# tag.net
KiCad netlist of a schematic drawn in EAGLE
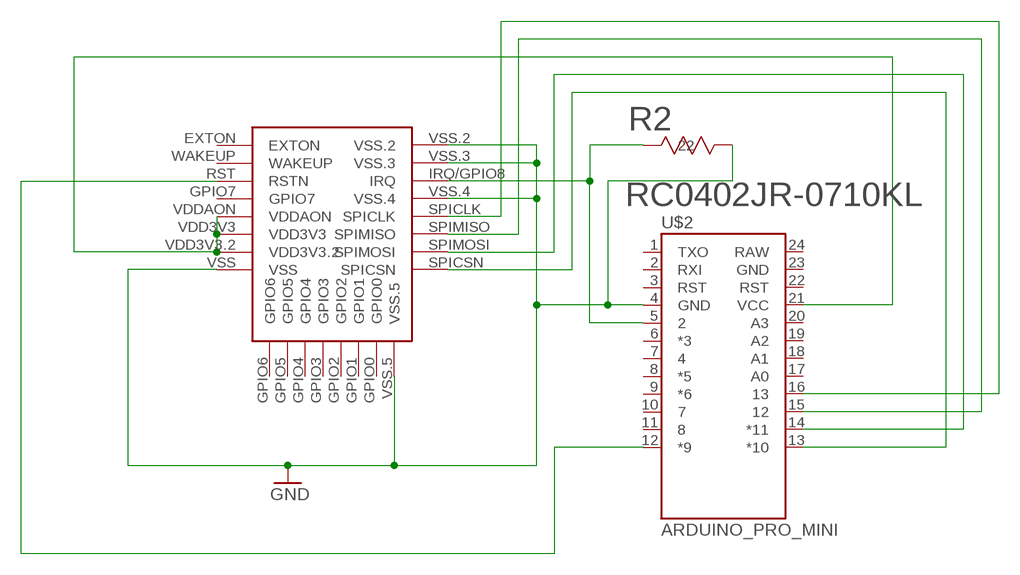
[diagram p0: schematic, sheet 1]

(export (version "E")
  (design (tool "Eeschema 10.0.6"))
  (components
    (comp (ref "R2")
      (value "RC0402JR-0710KL")
      (footprint "eagle-import:RC0402N")
      (fields
        (field (name "DIGIKEYPARTNUMBER") "31110KJRTRND")
        (field (name "MANUFACTURER_PART_NUMBER") "RC0402JR0710KL")
        (field (name "NEWARKPARTNUMBER") "67R9964")
        (field (name "COPYRIGHT") "Copyright C 2015 Accelerated Designs. All rights reserved")
      )
      (libsource (lib "eagle-import") (part "RC0402JR-0710KL"))
    )
    (comp (ref "U$1")
      (value "DWM1000")
      (footprint "eagle-import:DWM1000")
      (libsource (lib "eagle-import") (part "DWM1000"))
    )
    (comp (ref "U$2")
      (value "ARDUINO_PRO_MINI")
      (footprint "eagle-import:ARDUINO_PRO_MINI")
      (libsource (lib "eagle-import") (part "ARDUINO_PRO_MINI"))
    )
  )
  (nets
    (net (code "1") (name "GND") (class "Default")
      (node (ref "R2") (pin "1") (pinfunction "11_1") (pintype "passive"))
      (node (ref "U$1") (pin "VSS") (pinfunction "VSS_VSS") (pintype "bidirectional"))
      (node (ref "U$1") (pin "VSS.2") (pinfunction "VSS.2_VSS.2") (pintype "bidirectional"))
      (node (ref "U$1") (pin "VSS.3") (pinfunction "VSS.3_VSS.3") (pintype "bidirectional"))
      (node (ref "U$1") (pin "VSS.4") (pinfunction "VSS.4_VSS.4") (pintype "bidirectional"))
      (node (ref "U$1") (pin "VSS.5") (pinfunction "VSS.5_VSS.5") (pintype "bidirectional"))
      (node (ref "U$2") (pin "4") (pinfunction "GND_4") (pintype "bidirectional"))
    )
    (net (code "2") (name "Net-(R2-22)") (class "Default")
      (node (ref "R2") (pin "2") (pinfunction "22_2") (pintype "passive"))
      (node (ref "U$1") (pin "IRQ/GPIO8") (pinfunction "IRQ_IRQ/GPIO8") (pintype "bidirectional"))
      (node (ref "U$2") (pin "5") (pinfunction "2_5") (pintype "bidirectional"))
    )
    (net (code "3") (name "Net-(U$1-RSTN)") (class "Default")
      (node (ref "U$1") (pin "RST") (pinfunction "RSTN_RST") (pintype "bidirectional"))
      (node (ref "U$2") (pin "12") (pinfunction "*9_12") (pintype "bidirectional"))
    )
    (net (code "4") (name "Net-(U$2-*10)") (class "Default")
      (node (ref "U$1") (pin "SPICSN") (pinfunction "SPICSN_SPICSN") (pintype "bidirectional"))
      (node (ref "U$2") (pin "13") (pinfunction "*10_13") (pintype "bidirectional"))
    )
    (net (code "5") (name "Net-(U$2-*11)") (class "Default")
      (node (ref "U$1") (pin "SPIMOSI") (pinfunction "SPIMOSI_SPIMOSI") (pintype "bidirectional"))
      (node (ref "U$2") (pin "14") (pinfunction "*11_14") (pintype "bidirectional"))
    )
    (net (code "6") (name "Net-(U$2-12)") (class "Default")
      (node (ref "U$1") (pin "SPIMISO") (pinfunction "SPIMISO_SPIMISO") (pintype "bidirectional"))
      (node (ref "U$2") (pin "15") (pinfunction "12_15") (pintype "bidirectional"))
    )
    (net (code "7") (name "Net-(U$2-13)") (class "Default")
      (node (ref "U$1") (pin "SPICLK") (pinfunction "SPICLK_SPICLK") (pintype "bidirectional"))
      (node (ref "U$2") (pin "16") (pinfunction "13_16") (pintype "bidirectional"))
    )
    (net (code "8") (name "Net-(U$2-VCC)") (class "Default")
      (node (ref "U$1") (pin "VDD3V3") (pinfunction "VDD3V3_VDD3V3") (pintype "bidirectional"))
      (node (ref "U$1") (pin "VDD3V3.2") (pinfunction "VDD3V3.2_VDD3V3.2") (pintype "bidirectional"))
      (node (ref "U$1") (pin "VDDAON") (pinfunction "VDDAON_VDDAON") (pintype "bidirectional"))
      (node (ref "U$2") (pin "21") (pinfunction "VCC_21") (pintype "bidirectional"))
    )
    (net (code "9") (name "unconnected-(U$1-PadEXTON)") (class "Default")
      (node (ref "U$1") (pin "EXTON") (pinfunction "EXTON_EXTON") (pintype "bidirectional"))
    )
    (net (code "10") (name "unconnected-(U$1-PadGPIO0)") (class "Default")
      (node (ref "U$1") (pin "GPIO0") (pinfunction "GPIO0_GPIO0") (pintype "bidirectional"))
    )
    (net (code "11") (name "unconnected-(U$1-PadGPIO1)") (class "Default")
      (node (ref "U$1") (pin "GPIO1") (pinfunction "GPIO1_GPIO1") (pintype "bidirectional"))
    )
    (net (code "12") (name "unconnected-(U$1-PadGPIO2)") (class "Default")
      (node (ref "U$1") (pin "GPIO2") (pinfunction "GPIO2_GPIO2") (pintype "bidirectional"))
    )
    (net (code "13") (name "unconnected-(U$1-PadGPIO3)") (class "Default")
      (node (ref "U$1") (pin "GPIO3") (pinfunction "GPIO3_GPIO3") (pintype "bidirectional"))
    )
    (net (code "14") (name "unconnected-(U$1-PadGPIO4)") (class "Default")
      (node (ref "U$1") (pin "GPIO4") (pinfunction "GPIO4_GPIO4") (pintype "bidirectional"))
    )
    (net (code "15") (name "unconnected-(U$1-PadGPIO5)") (class "Default")
      (node (ref "U$1") (pin "GPIO5") (pinfunction "GPIO5_GPIO5") (pintype "bidirectional"))
    )
    (net (code "16") (name "unconnected-(U$1-PadGPIO6)") (class "Default")
      (node (ref "U$1") (pin "GPIO6") (pinfunction "GPIO6_GPIO6") (pintype "bidirectional"))
    )
    (net (code "17") (name "unconnected-(U$1-PadGPIO7)") (class "Default")
      (node (ref "U$1") (pin "GPIO7") (pinfunction "GPIO7_GPIO7") (pintype "bidirectional"))
    )
    (net (code "18") (name "unconnected-(U$1-PadWAKEUP)") (class "Default")
      (node (ref "U$1") (pin "WAKEUP") (pinfunction "WAKEUP_WAKEUP") (pintype "bidirectional"))
    )
    (net (code "19") (name "unconnected-(U$2-*3-Pad6)") (class "Default")
      (node (ref "U$2") (pin "6") (pinfunction "*3_6") (pintype "bidirectional"))
    )
    (net (code "20") (name "unconnected-(U$2-*5-Pad8)") (class "Default")
      (node (ref "U$2") (pin "8") (pinfunction "*5_8") (pintype "bidirectional"))
    )
    (net (code "21") (name "unconnected-(U$2-*6-Pad9)") (class "Default")
      (node (ref "U$2") (pin "9") (pinfunction "*6_9") (pintype "bidirectional"))
    )
    (net (code "22") (name "unconnected-(U$2-4-Pad7)") (class "Default")
      (node (ref "U$2") (pin "7") (pinfunction "4_7") (pintype "bidirectional"))
    )
    (net (code "23") (name "unconnected-(U$2-7-Pad10)") (class "Default")
      (node (ref "U$2") (pin "10") (pinfunction "7_10") (pintype "bidirectional"))
    )
    (net (code "24") (name "unconnected-(U$2-8-Pad11)") (class "Default")
      (node (ref "U$2") (pin "11") (pinfunction "8_11") (pintype "bidirectional"))
    )
    (net (code "25") (name "unconnected-(U$2-A0-Pad17)") (class "Default")
      (node (ref "U$2") (pin "17") (pinfunction "A0_17") (pintype "bidirectional"))
    )
    (net (code "26") (name "unconnected-(U$2-A1-Pad18)") (class "Default")
      (node (ref "U$2") (pin "18") (pinfunction "A1_18") (pintype "bidirectional"))
    )
    (net (code "27") (name "unconnected-(U$2-A2-Pad19)") (class "Default")
      (node (ref "U$2") (pin "19") (pinfunction "A2_19") (pintype "bidirectional"))
    )
    (net (code "28") (name "unconnected-(U$2-A3-Pad20)") (class "Default")
      (node (ref "U$2") (pin "20") (pinfunction "A3_20") (pintype "bidirectional"))
    )
    (net (code "29") (name "unconnected-(U$2-GND-Pad23)") (class "Default")
      (node (ref "U$2") (pin "23") (pinfunction "GND_23") (pintype "bidirectional"))
    )
    (net (code "30") (name "unconnected-(U$2-RAW-Pad24)") (class "Default")
      (node (ref "U$2") (pin "24") (pinfunction "RAW_24") (pintype "bidirectional"))
    )
    (net (code "31") (name "unconnected-(U$2-RST-Pad3)") (class "Default")
      (node (ref "U$2") (pin "3") (pinfunction "RST_3") (pintype "bidirectional"))
    )
    (net (code "32") (name "unconnected-(U$2-RST-Pad22)") (class "Default")
      (node (ref "U$2") (pin "22") (pinfunction "RST_22") (pintype "bidirectional"))
    )
    (net (code "33") (name "unconnected-(U$2-RXI-Pad2)") (class "Default")
      (node (ref "U$2") (pin "2") (pinfunction "RXI_2") (pintype "bidirectional"))
    )
    (net (code "34") (name "unconnected-(U$2-TXO-Pad1)") (class "Default")
      (node (ref "U$2") (pin "1") (pinfunction "TXO_1") (pintype "bidirectional"))
    )
  )
)
